# Board_Playground4Robotics_V3.net
KiCad netlist of a schematic drawn in EAGLE
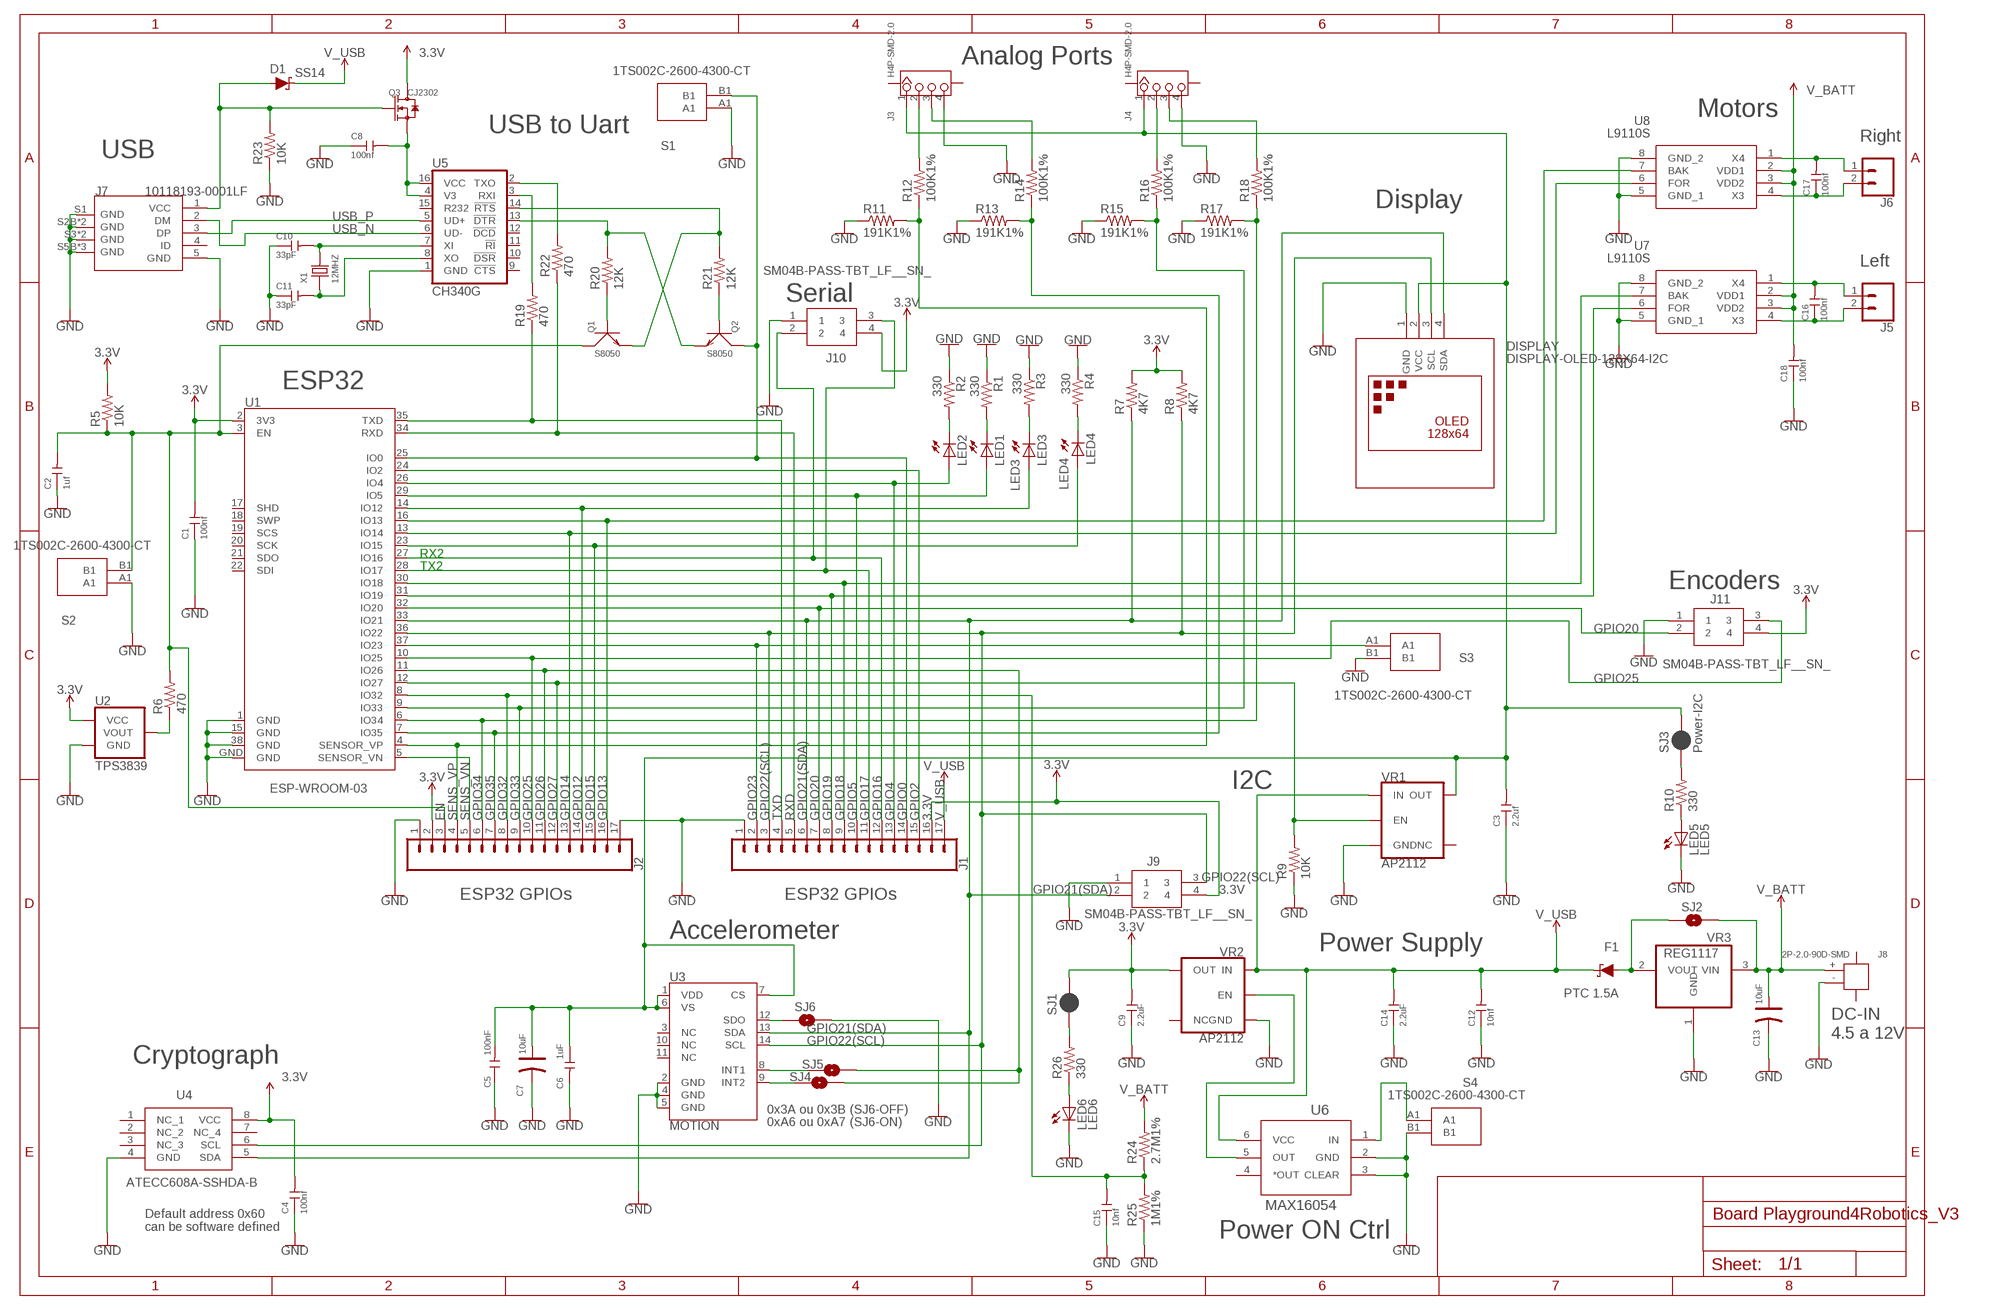
[diagram p0: schematic, sheet 1]

(export (version "E")
  (design (tool "Eeschema 10.0.6"))
  (components
    (comp (ref "C1")
      (value "100nf")
      (footprint "eagle-import:C0603")
      (fields (field (name "MPN") "CC0603KRX7R9BB104"))
      (libsource (lib "eagle-import") (part "CERAMIC-100NF-50V-10%-X7R(0603)"))
    )
    (comp (ref "C2")
      (value "1uf")
      (footprint "eagle-import:C0603")
      (fields (field (name "MPN") "CC0603KRX7R9BB104"))
      (libsource (lib "eagle-import") (part "CERAMIC-100NF-50V-10%-X7R(0603)"))
    )
    (comp (ref "C3")
      (value "2.2uf")
      (footprint "eagle-import:C0603")
      (fields (field (name "MPN") "CC0603KRX7R6BB225"))
      (libsource (lib "eagle-import") (part "CERAMIC-2.2UF-10V-10%-X7R(0603)"))
    )
    (comp (ref "C4")
      (value "100nf")
      (footprint "eagle-import:C0603")
      (fields (field (name "MPN") "CC0603KRX7R9BB104"))
      (libsource (lib "eagle-import") (part "CERAMIC-100NF-50V-10%-X7R(0603)"))
    )
    (comp (ref "C5")
      (value "100nF")
      (footprint "eagle-import:C0603")
      (libsource (lib "eagle-import") (part "C-0603"))
    )
    (comp (ref "C6")
      (value "1uF")
      (footprint "eagle-import:C0805")
      (libsource (lib "eagle-import") (part "C-0805"))
    )
    (comp (ref "C7")
      (value "10uF")
      (footprint "eagle-import:AVX-A")
      (libsource (lib "eagle-import") (part "CAP-AVX-A"))
    )
    (comp (ref "C8")
      (value "100nf")
      (footprint "eagle-import:C0603")
      (fields (field (name "MPN") "CC0603KRX7R9BB104"))
      (libsource (lib "eagle-import") (part "CERAMIC-100NF-50V-10%-X7R(0603)"))
    )
    (comp (ref "C9")
      (value "2.2uF")
      (footprint "eagle-import:C0603")
      (fields (field (name "MPN") "CC0603KRX7R6BB225"))
      (libsource (lib "eagle-import") (part "CERAMIC-2.2UF-10V-10%-X7R(0603)"))
    )
    (comp (ref "C10")
      (value "33pF")
      (footprint "eagle-import:C0603")
      (fields (field (name "MPN") "CC0603JRNPO9BN100"))
      (libsource (lib "eagle-import") (part "CERAMIC-10PF-50V-5%-NPO(0603)"))
    )
    (comp (ref "C11")
      (value "33pF")
      (footprint "eagle-import:C0603")
      (fields (field (name "MPN") "CC0603JRNPO9BN100"))
      (libsource (lib "eagle-import") (part "CERAMIC-10PF-50V-5%-NPO(0603)"))
    )
    (comp (ref "C12")
      (value "10nf")
      (footprint "eagle-import:C0603")
      (fields (field (name "MPN") "CC0603KRX7R9BB104"))
      (libsource (lib "eagle-import") (part "CERAMIC-100NF-50V-10%-X7R(0603)"))
    )
    (comp (ref "C13")
      (value "10uF")
      (footprint "eagle-import:AVX-A")
      (libsource (lib "eagle-import") (part "CAP-AVX-A"))
    )
    (comp (ref "C14")
      (value "2.2uF")
      (footprint "eagle-import:C0603")
      (fields (field (name "MPN") "CC0603KRX7R6BB225"))
      (libsource (lib "eagle-import") (part "CERAMIC-2.2UF-10V-10%-X7R(0603)"))
    )
    (comp (ref "C15")
      (value "10nf")
      (footprint "eagle-import:C0603")
      (fields (field (name "MPN") "CC0603KRX7R9BB104"))
      (libsource (lib "eagle-import") (part "CERAMIC-100NF-50V-10%-X7R(0603)"))
    )
    (comp (ref "C16")
      (value "100nf")
      (footprint "eagle-import:C0603")
      (fields (field (name "MPN") "CC0603KRX7R9BB104"))
      (libsource (lib "eagle-import") (part "CERAMIC-100NF-50V-10%-X7R(0603)"))
    )
    (comp (ref "C17")
      (value "100nf")
      (footprint "eagle-import:C0603")
      (fields (field (name "MPN") "CC0603KRX7R9BB104"))
      (libsource (lib "eagle-import") (part "CERAMIC-100NF-50V-10%-X7R(0603)"))
    )
    (comp (ref "C18")
      (value "100nf")
      (footprint "eagle-import:C0603")
      (fields (field (name "MPN") "CC0603KRX7R9BB104"))
      (libsource (lib "eagle-import") (part "CERAMIC-100NF-50V-10%-X7R(0603)"))
    )
    (comp (ref "D1")
      (value "SS14")
      (footprint "eagle-import:SMA-DIODE")
      (libsource (lib "eagle-import") (part "DIODE-SCHOTTKY-SS14"))
    )
    (comp (ref "DISPLAY")
      (value "DISPLAY-OLED-128X64-I2C")
      (footprint "eagle-import:DISPLAY-OLED-128X64-I2C")
      (libsource (lib "eagle-import") (part "DISPLAY-OLED-128X64-I2C"))
    )
    (comp (ref "F1")
      (value "PTC 1.5A")
      (footprint "eagle-import:SMA-DIODE")
      (libsource (lib "eagle-import") (part "DIODE-SCHOTTKY-SS14"))
    )
    (comp (ref "J1")
      (value "CONN_17")
      (footprint "eagle-import:1X17")
      (libsource (lib "eagle-import") (part "CONN_17"))
    )
    (comp (ref "J2")
      (value "CONN_17")
      (footprint "eagle-import:1X17")
      (libsource (lib "eagle-import") (part "CONN_17"))
    )
    (comp (ref "J3")
      (value "H4P-SMD-2.0")
      (footprint "eagle-import:HW4-SMD-2.0")
      (fields (field (name "SPICEPREFIX") "X"))
      (libsource (lib "eagle-import") (part "GROVE-CONNECTOR-SMD(4+2P-2.0)"))
    )
    (comp (ref "J4")
      (value "H4P-SMD-2.0")
      (footprint "eagle-import:HW4-SMD-2.0")
      (libsource (lib "eagle-import") (part "GROVE-CONNECTOR-SMD(4+2P-2.0)"))
    )
    (comp (ref "J5")
      (value "CONN_02POLAR")
      (footprint "eagle-import:MOLEX-1X2")
      (libsource (lib "eagle-import") (part "CONN_02POLAR"))
    )
    (comp (ref "J6")
      (value "CONN_02POLAR")
      (footprint "eagle-import:MOLEX-1X2")
      (libsource (lib "eagle-import") (part "CONN_02POLAR"))
    )
    (comp (ref "J7")
      (value "10118193-0001LF")
      (footprint "eagle-import:MICRO-USB5+6P-SMD-0.65-B")
      (libsource (lib "eagle-import") (part "MICRO-USB-SMD-B-(10118193-0001LF)"))
    )
    (comp (ref "J8")
      (value "2P-2.0-90D-SMD")
      (footprint "eagle-import:HW2-SMD-2.0-90D")
      (libsource (lib "eagle-import") (part "CONN-HEADER-SMD-PH-SIDE-(2P-2.0MM)"))
    )
    (comp (ref "J9")
      (value "SM04B-PASS-TBT_LF__SN_")
      (footprint "eagle-import:SM04B-PASS-TBT")
      (fields (field (name "MANUFACTURER_PART_NUMBER") "SM04B-PASS-TBT(LF)(SN)"))
      (libsource (lib "eagle-import") (part "SM04B-PASS-TBT_LF__SN_"))
    )
    (comp (ref "J10")
      (value "SM04B-PASS-TBT_LF__SN_")
      (footprint "eagle-import:SM04B-PASS-TBT")
      (fields (field (name "MANUFACTURER_PART_NUMBER") "SM04B-PASS-TBT(LF)(SN)"))
      (libsource (lib "eagle-import") (part "SM04B-PASS-TBT_LF__SN_"))
    )
    (comp (ref "J11")
      (value "SM04B-PASS-TBT_LF__SN_")
      (footprint "eagle-import:SM04B-PASS-TBT")
      (fields (field (name "MANUFACTURER_PART_NUMBER") "SM04B-PASS-TBT(LF)(SN)"))
      (libsource (lib "eagle-import") (part "SM04B-PASS-TBT_LF__SN_"))
    )
    (comp (ref "LED1")
      (value "LED1")
      (footprint "eagle-import:LED-0603")
      (libsource (lib "eagle-import") (part "LED0603"))
    )
    (comp (ref "LED2")
      (value "LED2")
      (footprint "eagle-import:LED-0603")
      (libsource (lib "eagle-import") (part "LED0603"))
    )
    (comp (ref "LED3")
      (value "LED3")
      (footprint "eagle-import:LED-0603")
      (libsource (lib "eagle-import") (part "LED0603"))
    )
    (comp (ref "LED4")
      (value "LED4")
      (footprint "eagle-import:LED-0603")
      (libsource (lib "eagle-import") (part "LED0603"))
    )
    (comp (ref "LED5")
      (value "LED5")
      (footprint "eagle-import:LED-0603")
      (libsource (lib "eagle-import") (part "LED0603"))
    )
    (comp (ref "LED6")
      (value "LED6")
      (footprint "eagle-import:LED-0603")
      (libsource (lib "eagle-import") (part "LED0603"))
    )
    (comp (ref "Q1")
      (value "S8050")
      (footprint "eagle-import:SOT-23")
      (libsource (lib "eagle-import") (part "SMD-TRANSISTORS-NPN-25V-500MW-S8050(SOT-23)"))
    )
    (comp (ref "Q2")
      (value "S8050")
      (footprint "eagle-import:SOT-23")
      (libsource (lib "eagle-import") (part "SMD-TRANSISTORS-NPN-25V-500MW-S8050(SOT-23)"))
    )
    (comp (ref "Q3")
      (value "CJ2302")
      (footprint "eagle-import:SOT-23")
      (libsource (lib "eagle-import") (part "SMD-MOSFET-N-CH-20V-2.1A-CJ2302(SOT-23)"))
    )
    (comp (ref "R1")
      (value "330")
      (footprint "eagle-import:0805")
      (libsource (lib "eagle-import") (part "RESISTOR0805-RES"))
    )
    (comp (ref "R2")
      (value "330")
      (footprint "eagle-import:0805")
      (libsource (lib "eagle-import") (part "RESISTOR0805-RES"))
    )
    (comp (ref "R3")
      (value "330")
      (footprint "eagle-import:0805")
      (libsource (lib "eagle-import") (part "RESISTOR0805-RES"))
    )
    (comp (ref "R4")
      (value "330")
      (footprint "eagle-import:0805")
      (libsource (lib "eagle-import") (part "RESISTOR0805-RES"))
    )
    (comp (ref "R5")
      (value "10K")
      (footprint "eagle-import:0805")
      (libsource (lib "eagle-import") (part "RESISTOR0805-RES"))
    )
    (comp (ref "R6")
      (value "470")
      (footprint "eagle-import:0805")
      (libsource (lib "eagle-import") (part "RESISTOR0805-RES"))
    )
    (comp (ref "R7")
      (value "4K7")
      (footprint "eagle-import:0805")
      (libsource (lib "eagle-import") (part "RESISTOR0805-RES"))
    )
    (comp (ref "R8")
      (value "4K7")
      (footprint "eagle-import:0805")
      (libsource (lib "eagle-import") (part "RESISTOR0805-RES"))
    )
    (comp (ref "R9")
      (value "10K")
      (footprint "eagle-import:0805")
      (libsource (lib "eagle-import") (part "RESISTOR0805-RES"))
    )
    (comp (ref "R10")
      (value "330")
      (footprint "eagle-import:0805")
      (libsource (lib "eagle-import") (part "RESISTOR0805-RES"))
    )
    (comp (ref "R11")
      (value "191K1%")
      (footprint "eagle-import:0805")
      (libsource (lib "eagle-import") (part "RESISTOR0805-RES"))
    )
    (comp (ref "R12")
      (value "100K1%")
      (footprint "eagle-import:0805")
      (fields (field (name "SPICEPREFIX") "R"))
      (libsource (lib "eagle-import") (part "RESISTOR0805-RES"))
    )
    (comp (ref "R13")
      (value "191K1%")
      (footprint "eagle-import:0805")
      (libsource (lib "eagle-import") (part "RESISTOR0805-RES"))
    )
    (comp (ref "R14")
      (value "100K1%")
      (footprint "eagle-import:0805")
      (libsource (lib "eagle-import") (part "RESISTOR0805-RES"))
    )
    (comp (ref "R15")
      (value "191K1%")
      (footprint "eagle-import:0805")
      (libsource (lib "eagle-import") (part "RESISTOR0805-RES"))
    )
    (comp (ref "R16")
      (value "100K1%")
      (footprint "eagle-import:0805")
      (fields (field (name "SPICEPREFIX") "R"))
      (libsource (lib "eagle-import") (part "RESISTOR0805-RES"))
    )
    (comp (ref "R17")
      (value "191K1%")
      (footprint "eagle-import:0805")
      (libsource (lib "eagle-import") (part "RESISTOR0805-RES"))
    )
    (comp (ref "R18")
      (value "100K1%")
      (footprint "eagle-import:0805")
      (libsource (lib "eagle-import") (part "RESISTOR0805-RES"))
    )
    (comp (ref "R19")
      (value "470")
      (footprint "eagle-import:0805")
      (libsource (lib "eagle-import") (part "RESISTOR0805-RES"))
    )
    (comp (ref "R20")
      (value "12K")
      (footprint "eagle-import:0805")
      (libsource (lib "eagle-import") (part "RESISTOR0805-RES"))
    )
    (comp (ref "R21")
      (value "12K")
      (footprint "eagle-import:0805")
      (libsource (lib "eagle-import") (part "RESISTOR0805-RES"))
    )
    (comp (ref "R22")
      (value "470")
      (footprint "eagle-import:0805")
      (libsource (lib "eagle-import") (part "RESISTOR0805-RES"))
    )
    (comp (ref "R23")
      (value "10K")
      (footprint "eagle-import:0805")
      (libsource (lib "eagle-import") (part "RESISTOR0805-RES"))
    )
    (comp (ref "R24")
      (value "2.7M1%")
      (footprint "eagle-import:0805")
      (libsource (lib "eagle-import") (part "RESISTOR0805-RES"))
    )
    (comp (ref "R25")
      (value "1M1%")
      (footprint "eagle-import:0805")
      (libsource (lib "eagle-import") (part "RESISTOR0805-RES"))
    )
    (comp (ref "R26")
      (value "330")
      (footprint "eagle-import:0805")
      (libsource (lib "eagle-import") (part "RESISTOR0805-RES"))
    )
    (comp (ref "S1")
      (value "1TS002C-2600-4300-CT")
      (footprint "eagle-import:1TS002C26004300CT")
      (libsource (lib "eagle-import") (part "1TS002C-2600-4300-CT"))
    )
    (comp (ref "S2")
      (value "1TS002C-2600-4300-CT")
      (footprint "eagle-import:1TS002C26004300CT")
      (libsource (lib "eagle-import") (part "1TS002C-2600-4300-CT"))
    )
    (comp (ref "S3")
      (value "1TS002C-2600-4300-CT")
      (footprint "eagle-import:1TS002C26004300CT")
      (libsource (lib "eagle-import") (part "1TS002C-2600-4300-CT"))
    )
    (comp (ref "S4")
      (value "1TS002C-2600-4300-CT")
      (footprint "eagle-import:1TS002C26004300CT")
      (libsource (lib "eagle-import") (part "1TS002C-2600-4300-CT"))
    )
    (comp (ref "SJ1")
      (value "Power-Led")
      (footprint "eagle-import:SMT-JUMPER_2_NC_PASTE_SILK")
      (libsource (lib "eagle-import") (part "JUMPER-SMT_2_NC_PASTE_SILK"))
    )
    (comp (ref "SJ2")
      (value "ADXL_ADDRESS")
      (footprint "eagle-import:SJ_2S-NO")
      (libsource (lib "eagle-import") (part "SOLDERJUMPERNO"))
    )
    (comp (ref "SJ3")
      (value "Power-I2C")
      (footprint "eagle-import:SMT-JUMPER_2_NC_PASTE_SILK")
      (libsource (lib "eagle-import") (part "JUMPER-SMT_2_NC_PASTE_SILK"))
    )
    (comp (ref "SJ4")
      (value "INT1")
      (footprint "eagle-import:SJ_2S-NO")
      (libsource (lib "eagle-import") (part "SOLDERJUMPERNO"))
    )
    (comp (ref "SJ5")
      (value "INT1")
      (footprint "eagle-import:SJ_2S-NO")
      (libsource (lib "eagle-import") (part "SOLDERJUMPERNO"))
    )
    (comp (ref "SJ6")
      (value "ADXL_ADDRESS")
      (footprint "eagle-import:SJ_2S-NO")
      (libsource (lib "eagle-import") (part "SOLDERJUMPERNO"))
    )
    (comp (ref "U1")
      (value "ESP-WROOM-03")
      (footprint "eagle-import:ESP-WROOM-03")
      (libsource (lib "eagle-import") (part "ESP-WROOM-03"))
    )
    (comp (ref "U2")
      (value "TPS3839")
      (footprint "eagle-import:SOT23-3")
      (libsource (lib "eagle-import") (part "V_SUPERVISOR"))
    )
    (comp (ref "U3")
      (value "MOTION")
      (footprint "eagle-import:LGA-14")
      (libsource (lib "eagle-import") (part "ADXL345"))
    )
    (comp (ref "U4")
      (value "ATECC608A-SSHDA-B")
      (footprint "eagle-import:SOIC127P600X175-8N")
      (fields (field (name "MOUSER_PART_NUMBER") "556-ATECC608ASSHDAB"))
      (libsource (lib "eagle-import") (part "ATECC608A-SSHDA-B"))
    )
    (comp (ref "U5")
      (value "CH340G")
      (footprint "eagle-import:SO016")
      (libsource (lib "eagle-import") (part "CH340GSMD"))
    )
    (comp (ref "U6")
      (value "MAX16054")
      (footprint "eagle-import:SOT23-6")
      (fields (field (name "MF") "Maxim Integrated") (field (name "MPN") "MAX16054AZT+T"))
      (libsource (lib "eagle-import") (part "MAX16054"))
    )
    (comp (ref "U7")
      (value "L9110S")
      (footprint "eagle-import:SOIC127P600X175-8N")
      (libsource (lib "eagle-import") (part "L9110S"))
    )
    (comp (ref "U8")
      (value "L9110S")
      (footprint "eagle-import:SOIC127P600X175-8N")
      (libsource (lib "eagle-import") (part "L9110S"))
    )
    (comp (ref "VR1")
      (value "AP2112")
      (footprint "eagle-import:SOT23-5")
      (libsource (lib "eagle-import") (part "V_REG_AP2112K-3.3V"))
    )
    (comp (ref "VR2")
      (value "AP2112")
      (footprint "eagle-import:SOT23-5")
      (libsource (lib "eagle-import") (part "V_REG_AP2112K-3.3V"))
    )
    (comp (ref "VR3")
      (value "REG1117")
      (footprint "eagle-import:SOT223")
      (libsource (lib "eagle-import") (part "REG1117"))
    )
    (comp (ref "X1")
      (value "12MHZ")
      (footprint "eagle-import:X2-SMD-5.0X3.2X1.3MM")
      (fields (field (name "MPN") "5032/2P"))
      (libsource (lib "eagle-import") (part "SMD-CRYSTAL-12MHZ-20PF-20PPM-40R(2P-5.0X3.2MM)"))
    )
  )
  (nets
    (net (code "1") (name "/EN") (class "Default")
      (node (ref "C2") (pin "2") (pinfunction "2_2") (pintype "passive"))
      (node (ref "J2") (pin "3") (pinfunction "3_3") (pintype "passive"))
      (node (ref "Q1") (pin "3") (pinfunction "C_3") (pintype "passive"))
      (node (ref "R5") (pin "1") (pinfunction "1_1") (pintype "passive"))
      (node (ref "R6") (pin "2") (pinfunction "2_2") (pintype "passive"))
      (node (ref "S2") (pin "B1") (pinfunction "B1_B1") (pintype "bidirectional"))
      (node (ref "U1") (pin "3") (pinfunction "EN_3") (pintype "bidirectional"))
    )
    (net (code "2") (name "/GPIO0") (class "Default")
      (node (ref "J1") (pin "14") (pinfunction "14_14") (pintype "passive"))
      (node (ref "Q2") (pin "3") (pinfunction "C_3") (pintype "passive"))
      (node (ref "S1") (pin "B1") (pinfunction "B1_B1") (pintype "bidirectional"))
      (node (ref "U1") (pin "25") (pinfunction "IO0_25") (pintype "bidirectional"))
    )
    (net (code "3") (name "/GPIO2") (class "Default")
      (node (ref "J1") (pin "15") (pinfunction "15_15") (pintype "passive"))
      (node (ref "U1") (pin "24") (pinfunction "IO2_24") (pintype "bidirectional"))
    )
    (net (code "4") (name "/GPIO4") (class "Default")
      (node (ref "J1") (pin "13") (pinfunction "13_13") (pintype "passive"))
      (node (ref "LED2") (pin "A") (pinfunction "A_A") (pintype "passive"))
      (node (ref "U1") (pin "26") (pinfunction "IO4_26") (pintype "bidirectional"))
    )
    (net (code "5") (name "/GPIO5") (class "Default")
      (node (ref "J1") (pin "10") (pinfunction "10_10") (pintype "passive"))
      (node (ref "LED1") (pin "A") (pinfunction "A_A") (pintype "passive"))
      (node (ref "U1") (pin "29") (pinfunction "IO5_29") (pintype "bidirectional"))
    )
    (net (code "6") (name "/GPIO12") (class "Default")
      (node (ref "J2") (pin "14") (pinfunction "14_14") (pintype "passive"))
      (node (ref "LED3") (pin "A") (pinfunction "A_A") (pintype "passive"))
      (node (ref "U1") (pin "14") (pinfunction "IO12_14") (pintype "bidirectional"))
    )
    (net (code "7") (name "/GPIO13") (class "Default")
      (node (ref "J2") (pin "16") (pinfunction "16_16") (pintype "passive"))
      (node (ref "U1") (pin "16") (pinfunction "IO13_16") (pintype "bidirectional"))
      (node (ref "U8") (pin "7") (pinfunction "BAK_7") (pintype "bidirectional"))
    )
    (net (code "8") (name "/GPIO14") (class "Default")
      (node (ref "J2") (pin "13") (pinfunction "13_13") (pintype "passive"))
      (node (ref "U1") (pin "13") (pinfunction "IO14_13") (pintype "bidirectional"))
      (node (ref "U8") (pin "6") (pinfunction "FOR_6") (pintype "bidirectional"))
    )
    (net (code "9") (name "/GPIO15") (class "Default")
      (node (ref "J2") (pin "15") (pinfunction "15_15") (pintype "passive"))
      (node (ref "LED4") (pin "A") (pinfunction "A_A") (pintype "passive"))
      (node (ref "U1") (pin "23") (pinfunction "IO15_23") (pintype "bidirectional"))
    )
    (net (code "10") (name "/GPIO16") (class "Default")
      (node (ref "J1") (pin "12") (pinfunction "12_12") (pintype "passive"))
      (node (ref "J10") (pin "2") (pinfunction "2_2") (pintype "bidirectional"))
      (node (ref "U1") (pin "27") (pinfunction "IO16_27") (pintype "bidirectional"))
    )
    (net (code "11") (name "/GPIO17") (class "Default")
      (node (ref "J1") (pin "11") (pinfunction "11_11") (pintype "passive"))
      (node (ref "J10") (pin "3") (pinfunction "3_3") (pintype "bidirectional"))
      (node (ref "U1") (pin "28") (pinfunction "IO17_28") (pintype "bidirectional"))
    )
    (net (code "12") (name "/GPIO18") (class "Default")
      (node (ref "J1") (pin "9") (pinfunction "9_9") (pintype "passive"))
      (node (ref "U1") (pin "30") (pinfunction "IO18_30") (pintype "bidirectional"))
      (node (ref "U7") (pin "7") (pinfunction "BAK_7") (pintype "bidirectional"))
    )
    (net (code "13") (name "/GPIO19") (class "Default")
      (node (ref "J1") (pin "8") (pinfunction "8_8") (pintype "passive"))
      (node (ref "U1") (pin "31") (pinfunction "IO19_31") (pintype "bidirectional"))
      (node (ref "U7") (pin "6") (pinfunction "FOR_6") (pintype "bidirectional"))
    )
    (net (code "14") (name "/GPIO20") (class "Default")
      (node (ref "J1") (pin "7") (pinfunction "7_7") (pintype "passive"))
      (node (ref "J11") (pin "2") (pinfunction "2_2") (pintype "bidirectional"))
      (node (ref "U1") (pin "32") (pinfunction "IO20_32") (pintype "bidirectional"))
    )
    (net (code "15") (name "/GPIO21(SDA)") (class "Default")
      (node (ref "DISPLAY") (pin "4") (pinfunction "SDA_4") (pintype "bidirectional"))
      (node (ref "J1") (pin "6") (pinfunction "6_6") (pintype "passive"))
      (node (ref "J9") (pin "2") (pinfunction "2_2") (pintype "bidirectional"))
      (node (ref "R7") (pin "1") (pinfunction "1_1") (pintype "passive"))
      (node (ref "U1") (pin "33") (pinfunction "IO21_33") (pintype "bidirectional"))
      (node (ref "U3") (pin "13") (pinfunction "SDA_13") (pintype "bidirectional"))
      (node (ref "U4") (pin "5") (pinfunction "SDA_5") (pintype "bidirectional"))
    )
    (net (code "16") (name "/GPIO22(SCL)") (class "Default")
      (node (ref "DISPLAY") (pin "3") (pinfunction "SCL_3") (pintype "bidirectional"))
      (node (ref "J1") (pin "3") (pinfunction "3_3") (pintype "passive"))
      (node (ref "J9") (pin "3") (pinfunction "3_3") (pintype "bidirectional"))
      (node (ref "R8") (pin "1") (pinfunction "1_1") (pintype "passive"))
      (node (ref "U1") (pin "36") (pinfunction "IO22_36") (pintype "bidirectional"))
      (node (ref "U3") (pin "14") (pinfunction "SCL_14") (pintype "bidirectional"))
      (node (ref "U4") (pin "6") (pinfunction "SCL_6") (pintype "bidirectional"))
    )
    (net (code "17") (name "/GPIO23") (class "Default")
      (node (ref "J1") (pin "2") (pinfunction "2_2") (pintype "passive"))
      (node (ref "S3") (pin "A1") (pinfunction "A1_A1") (pintype "bidirectional"))
      (node (ref "U1") (pin "37") (pinfunction "IO23_37") (pintype "bidirectional"))
    )
    (net (code "18") (name "/GPIO25") (class "Default")
      (node (ref "J11") (pin "3") (pinfunction "3_3") (pintype "bidirectional"))
      (node (ref "J2") (pin "10") (pinfunction "10_10") (pintype "passive"))
      (node (ref "U1") (pin "10") (pinfunction "IO25_10") (pintype "bidirectional"))
    )
    (net (code "19") (name "/GPIO26") (class "Default")
      (node (ref "J2") (pin "11") (pinfunction "11_11") (pintype "passive"))
      (node (ref "SJ4") (pin "2") (pinfunction "2_2") (pintype "passive"))
      (node (ref "SJ5") (pin "2") (pinfunction "2_2") (pintype "passive"))
      (node (ref "U1") (pin "11") (pinfunction "IO26_11") (pintype "bidirectional"))
    )
    (net (code "20") (name "/GPIO27") (class "Default")
      (node (ref "J2") (pin "12") (pinfunction "12_12") (pintype "passive"))
      (node (ref "R9") (pin "2") (pinfunction "2_2") (pintype "passive"))
      (node (ref "U1") (pin "12") (pinfunction "IO27_12") (pintype "bidirectional"))
      (node (ref "VR1") (pin "3") (pinfunction "EN_3") (pintype "input"))
    )
    (net (code "21") (name "/GPIO32") (class "Default")
      (node (ref "C15") (pin "2") (pinfunction "2_2") (pintype "passive"))
      (node (ref "J2") (pin "8") (pinfunction "8_8") (pintype "passive"))
      (node (ref "R24") (pin "1") (pinfunction "1_1") (pintype "passive"))
      (node (ref "R25") (pin "2") (pinfunction "2_2") (pintype "passive"))
      (node (ref "U1") (pin "8") (pinfunction "IO32_8") (pintype "bidirectional"))
    )
    (net (code "22") (name "/GPIO33") (class "Default")
      (node (ref "J2") (pin "9") (pinfunction "9_9") (pintype "passive"))
      (node (ref "R15") (pin "2") (pinfunction "2_2") (pintype "passive"))
      (node (ref "R16") (pin "1") (pinfunction "1_1") (pintype "passive"))
      (node (ref "U1") (pin "9") (pinfunction "IO33_9") (pintype "bidirectional"))
    )
    (net (code "23") (name "/GPIO34") (class "Default")
      (node (ref "J2") (pin "6") (pinfunction "6_6") (pintype "passive"))
      (node (ref "R17") (pin "2") (pinfunction "2_2") (pintype "passive"))
      (node (ref "R18") (pin "1") (pinfunction "1_1") (pintype "passive"))
      (node (ref "U1") (pin "6") (pinfunction "IO34_6") (pintype "bidirectional"))
    )
    (net (code "24") (name "/GPIO35") (class "Default")
      (node (ref "J2") (pin "7") (pinfunction "7_7") (pintype "passive"))
      (node (ref "R13") (pin "2") (pinfunction "2_2") (pintype "passive"))
      (node (ref "R14") (pin "1") (pinfunction "1_1") (pintype "passive"))
      (node (ref "U1") (pin "7") (pinfunction "IO35_7") (pintype "bidirectional"))
    )
    (net (code "25") (name "/RXD") (class "Default")
      (node (ref "J1") (pin "5") (pinfunction "5_5") (pintype "passive"))
      (node (ref "R22") (pin "1") (pinfunction "1_1") (pintype "passive"))
      (node (ref "U1") (pin "34") (pinfunction "RXD_34") (pintype "bidirectional"))
    )
    (net (code "26") (name "/SENS_VN") (class "Default")
      (node (ref "J2") (pin "5") (pinfunction "5_5") (pintype "passive"))
      (node (ref "U1") (pin "5") (pinfunction "SENSOR_VN_5") (pintype "bidirectional"))
    )
    (net (code "27") (name "/SENS_VP") (class "Default")
      (node (ref "J2") (pin "4") (pinfunction "4_4") (pintype "passive"))
      (node (ref "R11") (pin "2") (pinfunction "2_2") (pintype "passive"))
      (node (ref "R12") (pin "1") (pinfunction "1_1") (pintype "passive"))
      (node (ref "U1") (pin "4") (pinfunction "SENSOR_VP_4") (pintype "bidirectional"))
    )
    (net (code "28") (name "/TXD") (class "Default")
      (node (ref "J1") (pin "4") (pinfunction "4_4") (pintype "passive"))
      (node (ref "R19") (pin "1") (pinfunction "1_1") (pintype "passive"))
      (node (ref "U1") (pin "35") (pinfunction "TXD_35") (pintype "bidirectional"))
    )
    (net (code "29") (name "/USB_N") (class "Default")
      (node (ref "J7") (pin "2") (pinfunction "DM_2") (pintype "bidirectional"))
      (node (ref "U5") (pin "6") (pinfunction "UD-_6") (pintype "bidirectional"))
    )
    (net (code "30") (name "/USB_P") (class "Default")
      (node (ref "J7") (pin "3") (pinfunction "DP_3") (pintype "bidirectional"))
      (node (ref "U5") (pin "5") (pinfunction "UD+_5") (pintype "bidirectional"))
    )
    (net (code "31") (name "3.3V") (class "Default")
      (node (ref "C1") (pin "2") (pinfunction "2_2") (pintype "passive"))
      (node (ref "C4") (pin "2") (pinfunction "2_2") (pintype "passive"))
      (node (ref "C9") (pin "2") (pinfunction "2_2") (pintype "passive"))
      (node (ref "J1") (pin "16") (pinfunction "16_16") (pintype "passive"))
      (node (ref "J10") (pin "4") (pinfunction "4_4") (pintype "bidirectional"))
      (node (ref "J11") (pin "4") (pinfunction "4_4") (pintype "bidirectional"))
      (node (ref "J2") (pin "2") (pinfunction "2_2") (pintype "passive"))
      (node (ref "J9") (pin "4") (pinfunction "4_4") (pintype "bidirectional"))
      (node (ref "Q3") (pin "3") (pinfunction "D_3") (pintype "passive"))
      (node (ref "R5") (pin "2") (pinfunction "2_2") (pintype "passive"))
      (node (ref "R7") (pin "2") (pinfunction "2_2") (pintype "passive"))
      (node (ref "R8") (pin "2") (pinfunction "2_2") (pintype "passive"))
      (node (ref "SJ1") (pin "2") (pinfunction "2_2") (pintype "passive"))
      (node (ref "U1") (pin "2") (pinfunction "3V3_2") (pintype "bidirectional"))
      (node (ref "U2") (pin "3") (pinfunction "VCC_3") (pintype "input"))
      (node (ref "U4") (pin "8") (pinfunction "VCC_8") (pintype "bidirectional"))
      (node (ref "VR2") (pin "5") (pinfunction "OUT_5") (pintype "passive"))
    )
    (net (code "32") (name "GND") (class "Default")
      (node (ref "C1") (pin "1") (pinfunction "1_1") (pintype "passive"))
      (node (ref "C10") (pin "1") (pinfunction "1_1") (pintype "passive"))
      (node (ref "C11") (pin "1") (pinfunction "1_1") (pintype "passive"))
      (node (ref "C12") (pin "1") (pinfunction "1_1") (pintype "passive"))
      (node (ref "C13") (pin "-") (pinfunction "-_-") (pintype "passive"))
      (node (ref "C14") (pin "1") (pinfunction "1_1") (pintype "passive"))
      (node (ref "C15") (pin "1") (pinfunction "1_1") (pintype "passive"))
      (node (ref "C18") (pin "1") (pinfunction "1_1") (pintype "passive"))
      (node (ref "C2") (pin "1") (pinfunction "1_1") (pintype "passive"))
      (node (ref "C3") (pin "1") (pinfunction "1_1") (pintype "passive"))
      (node (ref "C4") (pin "1") (pinfunction "1_1") (pintype "passive"))
      (node (ref "C5") (pin "1") (pinfunction "1_1") (pintype "passive"))
      (node (ref "C6") (pin "2") (pinfunction "2_2") (pintype "passive"))
      (node (ref "C7") (pin "-") (pinfunction "-_-") (pintype "passive"))
      (node (ref "C8") (pin "1") (pinfunction "1_1") (pintype "passive"))
      (node (ref "C9") (pin "1") (pinfunction "1_1") (pintype "passive"))
      (node (ref "DISPLAY") (pin "1") (pinfunction "GND_1") (pintype "power_in"))
      (node (ref "J1") (pin "1") (pinfunction "1_1") (pintype "passive"))
      (node (ref "J10") (pin "1") (pinfunction "1_1") (pintype "bidirectional"))
      (node (ref "J11") (pin "1") (pinfunction "1_1") (pintype "bidirectional"))
      (node (ref "J2") (pin "1") (pinfunction "1_1") (pintype "passive"))
      (node (ref "J2") (pin "17") (pinfunction "17_17") (pintype "passive"))
      (node (ref "J3") (pin "4") (pinfunction "4_4") (pintype "bidirectional"))
      (node (ref "J4") (pin "4") (pinfunction "4_4") (pintype "bidirectional"))
      (node (ref "J7") (pin "5") (pinfunction "GND_5") (pintype "bidirectional"))
      (node (ref "J7") (pin "S1") (pinfunction "GND_S1") (pintype "bidirectional"))
      (node (ref "J7") (pin "S2B") (pinfunction "GND_S2B") (pintype "bidirectional"))
      (node (ref "J7") (pin "S2T") (pinfunction "GND_S2T") (pintype "bidirectional"))
      (node (ref "J7") (pin "S3") (pinfunction "GND_S3") (pintype "bidirectional"))
      (node (ref "J7") (pin "S4") (pinfunction "GND_S4") (pintype "bidirectional"))
      (node (ref "J7") (pin "S5B") (pinfunction "GND_S5B") (pintype "bidirectional"))
      (node (ref "J7") (pin "S5T") (pinfunction "GND_S5T") (pintype "bidirectional"))
      (node (ref "J7") (pin "S6") (pinfunction "GND_S6") (pintype "bidirectional"))
      (node (ref "J8") (pin "-") (pinfunction "2_-") (pintype "bidirectional"))
      (node (ref "J9") (pin "1") (pinfunction "1_1") (pintype "bidirectional"))
      (node (ref "LED5") (pin "C") (pinfunction "C_C") (pintype "passive"))
      (node (ref "LED6") (pin "C") (pinfunction "C_C") (pintype "passive"))
      (node (ref "R1") (pin "1") (pinfunction "1_1") (pintype "passive"))
      (node (ref "R11") (pin "1") (pinfunction "1_1") (pintype "passive"))
      (node (ref "R13") (pin "1") (pinfunction "1_1") (pintype "passive"))
      (node (ref "R15") (pin "1") (pinfunction "1_1") (pintype "passive"))
      (node (ref "R17") (pin "1") (pinfunction "1_1") (pintype "passive"))
      (node (ref "R2") (pin "1") (pinfunction "1_1") (pintype "passive"))
      (node (ref "R23") (pin "1") (pinfunction "1_1") (pintype "passive"))
      (node (ref "R25") (pin "1") (pinfunction "1_1") (pintype "passive"))
      (node (ref "R3") (pin "1") (pinfunction "1_1") (pintype "passive"))
      (node (ref "R4") (pin "1") (pinfunction "1_1") (pintype "passive"))
      (node (ref "R9") (pin "1") (pinfunction "1_1") (pintype "passive"))
      (node (ref "S1") (pin "A1") (pinfunction "A1_A1") (pintype "bidirectional"))
      (node (ref "S2") (pin "A1") (pinfunction "A1_A1") (pintype "bidirectional"))
      (node (ref "S3") (pin "B1") (pinfunction "B1_B1") (pintype "bidirectional"))
      (node (ref "S4") (pin "B1") (pinfunction "B1_B1") (pintype "bidirectional"))
      (node (ref "SJ6") (pin "2") (pinfunction "2_2") (pintype "passive"))
      (node (ref "U1") (pin "1") (pinfunction "GND_1") (pintype "bidirectional"))
      (node (ref "U1") (pin "15") (pinfunction "GND_15") (pintype "bidirectional"))
      (node (ref "U1") (pin "38") (pinfunction "GND_38") (pintype "bidirectional"))
      (node (ref "U1") (pin "GND") (pinfunction "GND_GND") (pintype "bidirectional"))
      (node (ref "U2") (pin "1") (pinfunction "GND_1") (pintype "input"))
      (node (ref "U3") (pin "2") (pinfunction "GND_2") (pintype "bidirectional"))
      (node (ref "U3") (pin "4") (pinfunction "GND_4") (pintype "bidirectional"))
      (node (ref "U3") (pin "5") (pinfunction "GND_5") (pintype "bidirectional"))
      (node (ref "U4") (pin "4") (pinfunction "GND_4") (pintype "bidirectional"))
      (node (ref "U5") (pin "1") (pinfunction "GND_1") (pintype "bidirectional"))
      (node (ref "U6") (pin "2") (pinfunction "GND_2") (pintype "power_in"))
      (node (ref "U6") (pin "3") (pinfunction "CLEAR_3") (pintype "input"))
      (node (ref "U7") (pin "5") (pinfunction "GND_1_5") (pintype "bidirectional"))
      (node (ref "U7") (pin "8") (pinfunction "GND_2_8") (pintype "bidirectional"))
      (node (ref "U8") (pin "5") (pinfunction "GND_1_5") (pintype "bidirectional"))
      (node (ref "U8") (pin "8") (pinfunction "GND_2_8") (pintype "bidirectional"))
      (node (ref "VR1") (pin "2") (pinfunction "GND_2") (pintype "input"))
      (node (ref "VR2") (pin "2") (pinfunction "GND_2") (pintype "input"))
      (node (ref "VR3") (pin "1") (pinfunction "GND_1") (pintype "power_in"))
    )
    (net (code "33") (name "Net-(DISPLAY-VCC)") (class "Default")
      (node (ref "C3") (pin "2") (pinfunction "2_2") (pintype "passive"))
      (node (ref "C5") (pin "2") (pinfunction "2_2") (pintype "passive"))
      (node (ref "C6") (pin "1") (pinfunction "1_1") (pintype "passive"))
      (node (ref "C7") (pin "+") (pinfunction "+_+") (pintype "passive"))
      (node (ref "DISPLAY") (pin "2") (pinfunction "VCC_2") (pintype "power_in"))
      (node (ref "J3") (pin "1") (pinfunction "1_1") (pintype "bidirectional"))
      (node (ref "J4") (pin "1") (pinfunction "1_1") (pintype "bidirectional"))
      (node (ref "SJ3") (pin "2") (pinfunction "2_2") (pintype "passive"))
      (node (ref "U3") (pin "1") (pinfunction "VDD_1") (pintype "bidirectional"))
      (node (ref "U3") (pin "6") (pinfunction "VS_6") (pintype "bidirectional"))
      (node (ref "U3") (pin "7") (pinfunction "CS_7") (pintype "bidirectional"))
      (node (ref "VR1") (pin "5") (pinfunction "OUT_5") (pintype "passive"))
    )
    (net (code "34") (name "Net-(J3-Pad2)") (class "Default")
      (node (ref "J3") (pin "2") (pinfunction "2_2") (pintype "bidirectional"))
      (node (ref "R12") (pin "2") (pinfunction "2_2") (pintype "passive"))
    )
    (net (code "35") (name "Net-(J3-Pad3)") (class "Default")
      (node (ref "J3") (pin "3") (pinfunction "3_3") (pintype "bidirectional"))
      (node (ref "R14") (pin "2") (pinfunction "2_2") (pintype "passive"))
    )
    (net (code "36") (name "Net-(J4-Pad2)") (class "Default")
      (node (ref "J4") (pin "2") (pinfunction "2_2") (pintype "bidirectional"))
      (node (ref "R16") (pin "2") (pinfunction "2_2") (pintype "passive"))
    )
    (net (code "37") (name "Net-(J4-Pad3)") (class "Default")
      (node (ref "J4") (pin "3") (pinfunction "3_3") (pintype "bidirectional"))
      (node (ref "R18") (pin "2") (pinfunction "2_2") (pintype "passive"))
    )
    (net (code "38") (name "Net-(J7-VCC)") (class "Default")
      (node (ref "D1") (pin "A") (pinfunction "A_A") (pintype "passive"))
      (node (ref "J7") (pin "1") (pinfunction "VCC_1") (pintype "bidirectional"))
      (node (ref "Q3") (pin "1") (pinfunction "G_1") (pintype "passive"))
      (node (ref "R23") (pin "2") (pinfunction "2_2") (pintype "passive"))
    )
    (net (code "39") (name "Net-(LED1-PadC)") (class "Default")
      (node (ref "LED1") (pin "C") (pinfunction "C_C") (pintype "passive"))
      (node (ref "R1") (pin "2") (pinfunction "2_2") (pintype "passive"))
    )
    (net (code "40") (name "Net-(LED2-PadC)") (class "Default")
      (node (ref "LED2") (pin "C") (pinfunction "C_C") (pintype "passive"))
      (node (ref "R2") (pin "2") (pinfunction "2_2") (pintype "passive"))
    )
    (net (code "41") (name "Net-(LED3-PadC)") (class "Default")
      (node (ref "LED3") (pin "C") (pinfunction "C_C") (pintype "passive"))
      (node (ref "R3") (pin "2") (pinfunction "2_2") (pintype "passive"))
    )
    (net (code "42") (name "Net-(LED4-PadC)") (class "Default")
      (node (ref "LED4") (pin "C") (pinfunction "C_C") (pintype "passive"))
      (node (ref "R4") (pin "2") (pinfunction "2_2") (pintype "passive"))
    )
    (net (code "43") (name "Net-(LED5-PadA)") (class "Default")
      (node (ref "LED5") (pin "A") (pinfunction "A_A") (pintype "passive"))
      (node (ref "R10") (pin "1") (pinfunction "1_1") (pintype "passive"))
    )
    (net (code "44") (name "Net-(LED6-PadA)") (class "Default")
      (node (ref "LED6") (pin "A") (pinfunction "A_A") (pintype "passive"))
      (node (ref "R26") (pin "1") (pinfunction "1_1") (pintype "passive"))
    )
    (net (code "45") (name "Net-(Q1-B)") (class "Default")
      (node (ref "Q1") (pin "1") (pinfunction "B_1") (pintype "passive"))
      (node (ref "R20") (pin "1") (pinfunction "1_1") (pintype "passive"))
    )
    (net (code "46") (name "Net-(Q1-E)") (class "Default")
      (node (ref "Q1") (pin "2") (pinfunction "E_2") (pintype "passive"))
      (node (ref "R21") (pin "2") (pinfunction "2_2") (pintype "passive"))
      (node (ref "U5") (pin "14") (pinfunction "~{RTS}_14") (pintype "bidirectional"))
    )
    (net (code "47") (name "Net-(Q2-B)") (class "Default")
      (node (ref "Q2") (pin "1") (pinfunction "B_1") (pintype "passive"))
      (node (ref "R21") (pin "1") (pinfunction "1_1") (pintype "passive"))
    )
    (net (code "48") (name "Net-(Q2-E)") (class "Default")
      (node (ref "Q2") (pin "2") (pinfunction "E_2") (pintype "passive"))
      (node (ref "R20") (pin "2") (pinfunction "2_2") (pintype "passive"))
      (node (ref "U5") (pin "13") (pinfunction "~{DTR}_13") (pintype "bidirectional"))
    )
    (net (code "49") (name "Net-(Q3-S)") (class "Default")
      (node (ref "C8") (pin "2") (pinfunction "2_2") (pintype "passive"))
      (node (ref "Q3") (pin "2") (pinfunction "S_2") (pintype "passive"))
      (node (ref "U5") (pin "16") (pinfunction "VCC_16") (pintype "bidirectional"))
      (node (ref "U5") (pin "4") (pinfunction "V3_4") (pintype "bidirectional"))
    )
    (net (code "50") (name "Net-(R10-Pad2)") (class "Default")
      (node (ref "R10") (pin "2") (pinfunction "2_2") (pintype "passive"))
      (node (ref "SJ3") (pin "1") (pinfunction "1_1") (pintype "passive"))
    )
    (net (code "51") (name "Net-(R26-Pad2)") (class "Default")
      (node (ref "R26") (pin "2") (pinfunction "2_2") (pintype "passive"))
      (node (ref "SJ1") (pin "1") (pinfunction "1_1") (pintype "passive"))
    )
    (net (code "52") (name "Net-(U2-VOUT)") (class "Default")
      (node (ref "R6") (pin "1") (pinfunction "1_1") (pintype "passive"))
      (node (ref "U2") (pin "2") (pinfunction "VOUT_2") (pintype "output"))
    )
    (net (code "53") (name "Net-(U3-INT1)") (class "Default")
      (node (ref "SJ5") (pin "1") (pinfunction "1_1") (pintype "passive"))
      (node (ref "U3") (pin "8") (pinfunction "INT1_8") (pintype "bidirectional"))
    )
    (net (code "54") (name "Net-(U3-INT2)") (class "Default")
      (node (ref "SJ4") (pin "1") (pinfunction "1_1") (pintype "passive"))
      (node (ref "U3") (pin "9") (pinfunction "INT2_9") (pintype "bidirectional"))
    )
    (net (code "55") (name "Net-(U3-SDO)") (class "Default")
      (node (ref "SJ6") (pin "1") (pinfunction "1_1") (pintype "passive"))
      (node (ref "U3") (pin "12") (pinfunction "SDO_12") (pintype "bidirectional"))
    )
    (net (code "56") (name "Net-(U5-RXI)") (class "Default")
      (node (ref "R19") (pin "2") (pinfunction "2_2") (pintype "passive"))
      (node (ref "U5") (pin "3") (pinfunction "RXI_3") (pintype "bidirectional"))
    )
    (net (code "57") (name "Net-(U5-TXO)") (class "Default")
      (node (ref "R22") (pin "2") (pinfunction "2_2") (pintype "passive"))
      (node (ref "U5") (pin "2") (pinfunction "TXO_2") (pintype "bidirectional"))
    )
    (net (code "58") (name "Net-(U5-XI)") (class "Default")
      (node (ref "C10") (pin "2") (pinfunction "2_2") (pintype "passive"))
      (node (ref "U5") (pin "7") (pinfunction "XI_7") (pintype "bidirectional"))
      (node (ref "X1") (pin "2") (pinfunction "2_2") (pintype "passive"))
    )
    (net (code "59") (name "Net-(U5-XO)") (class "Default")
      (node (ref "C11") (pin "2") (pinfunction "2_2") (pintype "passive"))
      (node (ref "U5") (pin "8") (pinfunction "XO_8") (pintype "bidirectional"))
      (node (ref "X1") (pin "1") (pinfunction "1_1") (pintype "passive"))
    )
    (net (code "60") (name "Net-(U6-IN)") (class "Default")
      (node (ref "S4") (pin "A1") (pinfunction "A1_A1") (pintype "bidirectional"))
      (node (ref "U6") (pin "1") (pinfunction "IN_1") (pintype "input"))
    )
    (net (code "61") (name "Net-(U6-OUT)") (class "Default")
      (node (ref "U6") (pin "5") (pinfunction "OUT_5") (pintype "output"))
      (node (ref "VR2") (pin "3") (pinfunction "EN_3") (pintype "input"))
    )
    (net (code "62") (name "Net-(U7-X3)") (class "Default")
      (node (ref "C16") (pin "1") (pinfunction "1_1") (pintype "passive"))
      (node (ref "J5") (pin "2") (pinfunction "2_2") (pintype "passive"))
      (node (ref "U7") (pin "4") (pinfunction "X3_4") (pintype "bidirectional"))
    )
    (net (code "63") (name "Net-(U7-X4)") (class "Default")
      (node (ref "C16") (pin "2") (pinfunction "2_2") (pintype "passive"))
      (node (ref "J5") (pin "1") (pinfunction "1_1") (pintype "passive"))
      (node (ref "U7") (pin "1") (pinfunction "X4_1") (pintype "bidirectional"))
    )
    (net (code "64") (name "Net-(U8-X3)") (class "Default")
      (node (ref "C17") (pin "1") (pinfunction "1_1") (pintype "passive"))
      (node (ref "J6") (pin "2") (pinfunction "2_2") (pintype "passive"))
      (node (ref "U8") (pin "4") (pinfunction "X3_4") (pintype "bidirectional"))
    )
    (net (code "65") (name "Net-(U8-X4)") (class "Default")
      (node (ref "C17") (pin "2") (pinfunction "2_2") (pintype "passive"))
      (node (ref "J6") (pin "1") (pinfunction "1_1") (pintype "passive"))
      (node (ref "U8") (pin "1") (pinfunction "X4_1") (pintype "bidirectional"))
    )
    (net (code "66") (name "Net-(VR3-VOUT)") (class "Default")
      (node (ref "F1") (pin "A") (pinfunction "A_A") (pintype "passive"))
      (node (ref "SJ2") (pin "1") (pinfunction "1_1") (pintype "passive"))
      (node (ref "VR3") (pin "2") (pinfunction "VOUT_2") (pintype "output"))
    )
    (net (code "67") (name "V_BATT") (class "Default")
      (node (ref "C13") (pin "+") (pinfunction "+_+") (pintype "passive"))
      (node (ref "C18") (pin "2") (pinfunction "2_2") (pintype "passive"))
      (node (ref "J8") (pin "+") (pinfunction "1_+") (pintype "bidirectional"))
      (node (ref "R24") (pin "2") (pinfunction "2_2") (pintype "passive"))
      (node (ref "SJ2") (pin "2") (pinfunction "2_2") (pintype "passive"))
      (node (ref "U7") (pin "2") (pinfunction "VDD1_2") (pintype "bidirectional"))
      (node (ref "U7") (pin "3") (pinfunction "VDD2_3") (pintype "bidirectional"))
      (node (ref "U8") (pin "2") (pinfunction "VDD1_2") (pintype "bidirectional"))
      (node (ref "U8") (pin "3") (pinfunction "VDD2_3") (pintype "bidirectional"))
      (node (ref "VR3") (pin "3") (pinfunction "VIN_3") (pintype "input"))
    )
    (net (code "68") (name "V_USB") (class "Default")
      (node (ref "C12") (pin "2") (pinfunction "2_2") (pintype "passive"))
      (node (ref "C14") (pin "2") (pinfunction "2_2") (pintype "passive"))
      (node (ref "D1") (pin "C") (pinfunction "C_C") (pintype "passive"))
      (node (ref "F1") (pin "C") (pinfunction "C_C") (pintype "passive"))
      (node (ref "J1") (pin "17") (pinfunction "17_17") (pintype "passive"))
      (node (ref "U6") (pin "6") (pinfunction "VCC_6") (pintype "power_in"))
      (node (ref "VR1") (pin "1") (pinfunction "IN_1") (pintype "input"))
      (node (ref "VR2") (pin "1") (pinfunction "IN_1") (pintype "input"))
    )
    (net (code "69") (name "unconnected-(J3-PadSS1)") (class "Default")
      (node (ref "J3") (pin "SS1") (pinfunction "SS1_SS1") (pintype "bidirectional"))
    )
    (net (code "70") (name "unconnected-(J3-PadSS2)") (class "Default")
      (node (ref "J3") (pin "SS2") (pinfunction "SS2_SS2") (pintype "bidirectional"))
    )
    (net (code "71") (name "unconnected-(J4-PadSS1)") (class "Default")
      (node (ref "J4") (pin "SS1") (pinfunction "SS1_SS1") (pintype "bidirectional"))
    )
    (net (code "72") (name "unconnected-(J4-PadSS2)") (class "Default")
      (node (ref "J4") (pin "SS2") (pinfunction "SS2_SS2") (pintype "bidirectional"))
    )
    (net (code "73") (name "unconnected-(J7-ID-Pad4)") (class "Default")
      (node (ref "J7") (pin "4") (pinfunction "ID_4") (pintype "bidirectional"))
    )
    (net (code "74") (name "unconnected-(J8-Pad3)") (class "Default")
      (node (ref "J8") (pin "3") (pinfunction "3_3") (pintype "bidirectional"))
    )
    (net (code "75") (name "unconnected-(J8-Pad4)") (class "Default")
      (node (ref "J8") (pin "4") (pinfunction "4_4") (pintype "bidirectional"))
    )
    (net (code "76") (name "unconnected-(U1-SCK-Pad20)") (class "Default")
      (node (ref "U1") (pin "20") (pinfunction "SCK_20") (pintype "bidirectional"))
    )
    (net (code "77") (name "unconnected-(U1-SCS-Pad19)") (class "Default")
      (node (ref "U1") (pin "19") (pinfunction "SCS_19") (pintype "bidirectional"))
    )
    (net (code "78") (name "unconnected-(U1-SDI-Pad22)") (class "Default")
      (node (ref "U1") (pin "22") (pinfunction "SDI_22") (pintype "bidirectional"))
    )
    (net (code "79") (name "unconnected-(U1-SDO-Pad21)") (class "Default")
      (node (ref "U1") (pin "21") (pinfunction "SDO_21") (pintype "bidirectional"))
    )
    (net (code "80") (name "unconnected-(U1-SHD-Pad17)") (class "Default")
      (node (ref "U1") (pin "17") (pinfunction "SHD_17") (pintype "bidirectional"))
    )
    (net (code "81") (name "unconnected-(U1-SWP-Pad18)") (class "Default")
      (node (ref "U1") (pin "18") (pinfunction "SWP_18") (pintype "bidirectional"))
    )
    (net (code "82") (name "unconnected-(U3-NC-Pad3)") (class "Default")
      (node (ref "U3") (pin "3") (pinfunction "NC_3") (pintype "bidirectional"))
    )
    (net (code "83") (name "unconnected-(U3-NC-Pad10)") (class "Default")
      (node (ref "U3") (pin "10") (pinfunction "NC_10") (pintype "bidirectional"))
    )
    (net (code "84") (name "unconnected-(U3-NC-Pad11)") (class "Default")
      (node (ref "U3") (pin "11") (pinfunction "NC_11") (pintype "bidirectional"))
    )
    (net (code "85") (name "unconnected-(U4-NC_1-Pad1)") (class "Default")
      (node (ref "U4") (pin "1") (pinfunction "NC_1_1") (pintype "bidirectional"))
    )
    (net (code "86") (name "unconnected-(U4-NC_2-Pad2)") (class "Default")
      (node (ref "U4") (pin "2") (pinfunction "NC_2_2") (pintype "bidirectional"))
    )
    (net (code "87") (name "unconnected-(U4-NC_3-Pad3)") (class "Default")
      (node (ref "U4") (pin "3") (pinfunction "NC_3_3") (pintype "bidirectional"))
    )
    (net (code "88") (name "unconnected-(U4-NC_4-Pad7)") (class "Default")
      (node (ref "U4") (pin "7") (pinfunction "NC_4_7") (pintype "bidirectional"))
    )
    (net (code "89") (name "unconnected-(U5-R232-Pad15)") (class "Default")
      (node (ref "U5") (pin "15") (pinfunction "R232_15") (pintype "bidirectional"))
    )
    (net (code "90") (name "unconnected-(U5-~{CTS}-Pad9)") (class "Default")
      (node (ref "U5") (pin "9") (pinfunction "~{CTS}_9") (pintype "bidirectional"))
    )
    (net (code "91") (name "unconnected-(U5-~{DCD}-Pad12)") (class "Default")
      (node (ref "U5") (pin "12") (pinfunction "~{DCD}_12") (pintype "bidirectional"))
    )
    (net (code "92") (name "unconnected-(U5-~{DSR}-Pad10)") (class "Default")
      (node (ref "U5") (pin "10") (pinfunction "~{DSR}_10") (pintype "bidirectional"))
    )
    (net (code "93") (name "unconnected-(U5-~{RI}-Pad11)") (class "Default")
      (node (ref "U5") (pin "11") (pinfunction "~{RI}_11") (pintype "bidirectional"))
    )
    (net (code "94") (name "unconnected-(U6-*OUT-Pad4)") (class "Default")
      (node (ref "U6") (pin "4") (pinfunction "*OUT_4") (pintype "output"))
    )
    (net (code "95") (name "unconnected-(VR1-NC-Pad4)") (class "Default")
      (node (ref "VR1") (pin "4") (pinfunction "NC_4") (pintype "no_connect"))
    )
    (net (code "96") (name "unconnected-(VR2-NC-Pad4)") (class "Default")
      (node (ref "VR2") (pin "4") (pinfunction "NC_4") (pintype "no_connect"))
    )
  )
)
